# Sheet_2.net
KiCad netlist of a schematic drawn in Altium Designer
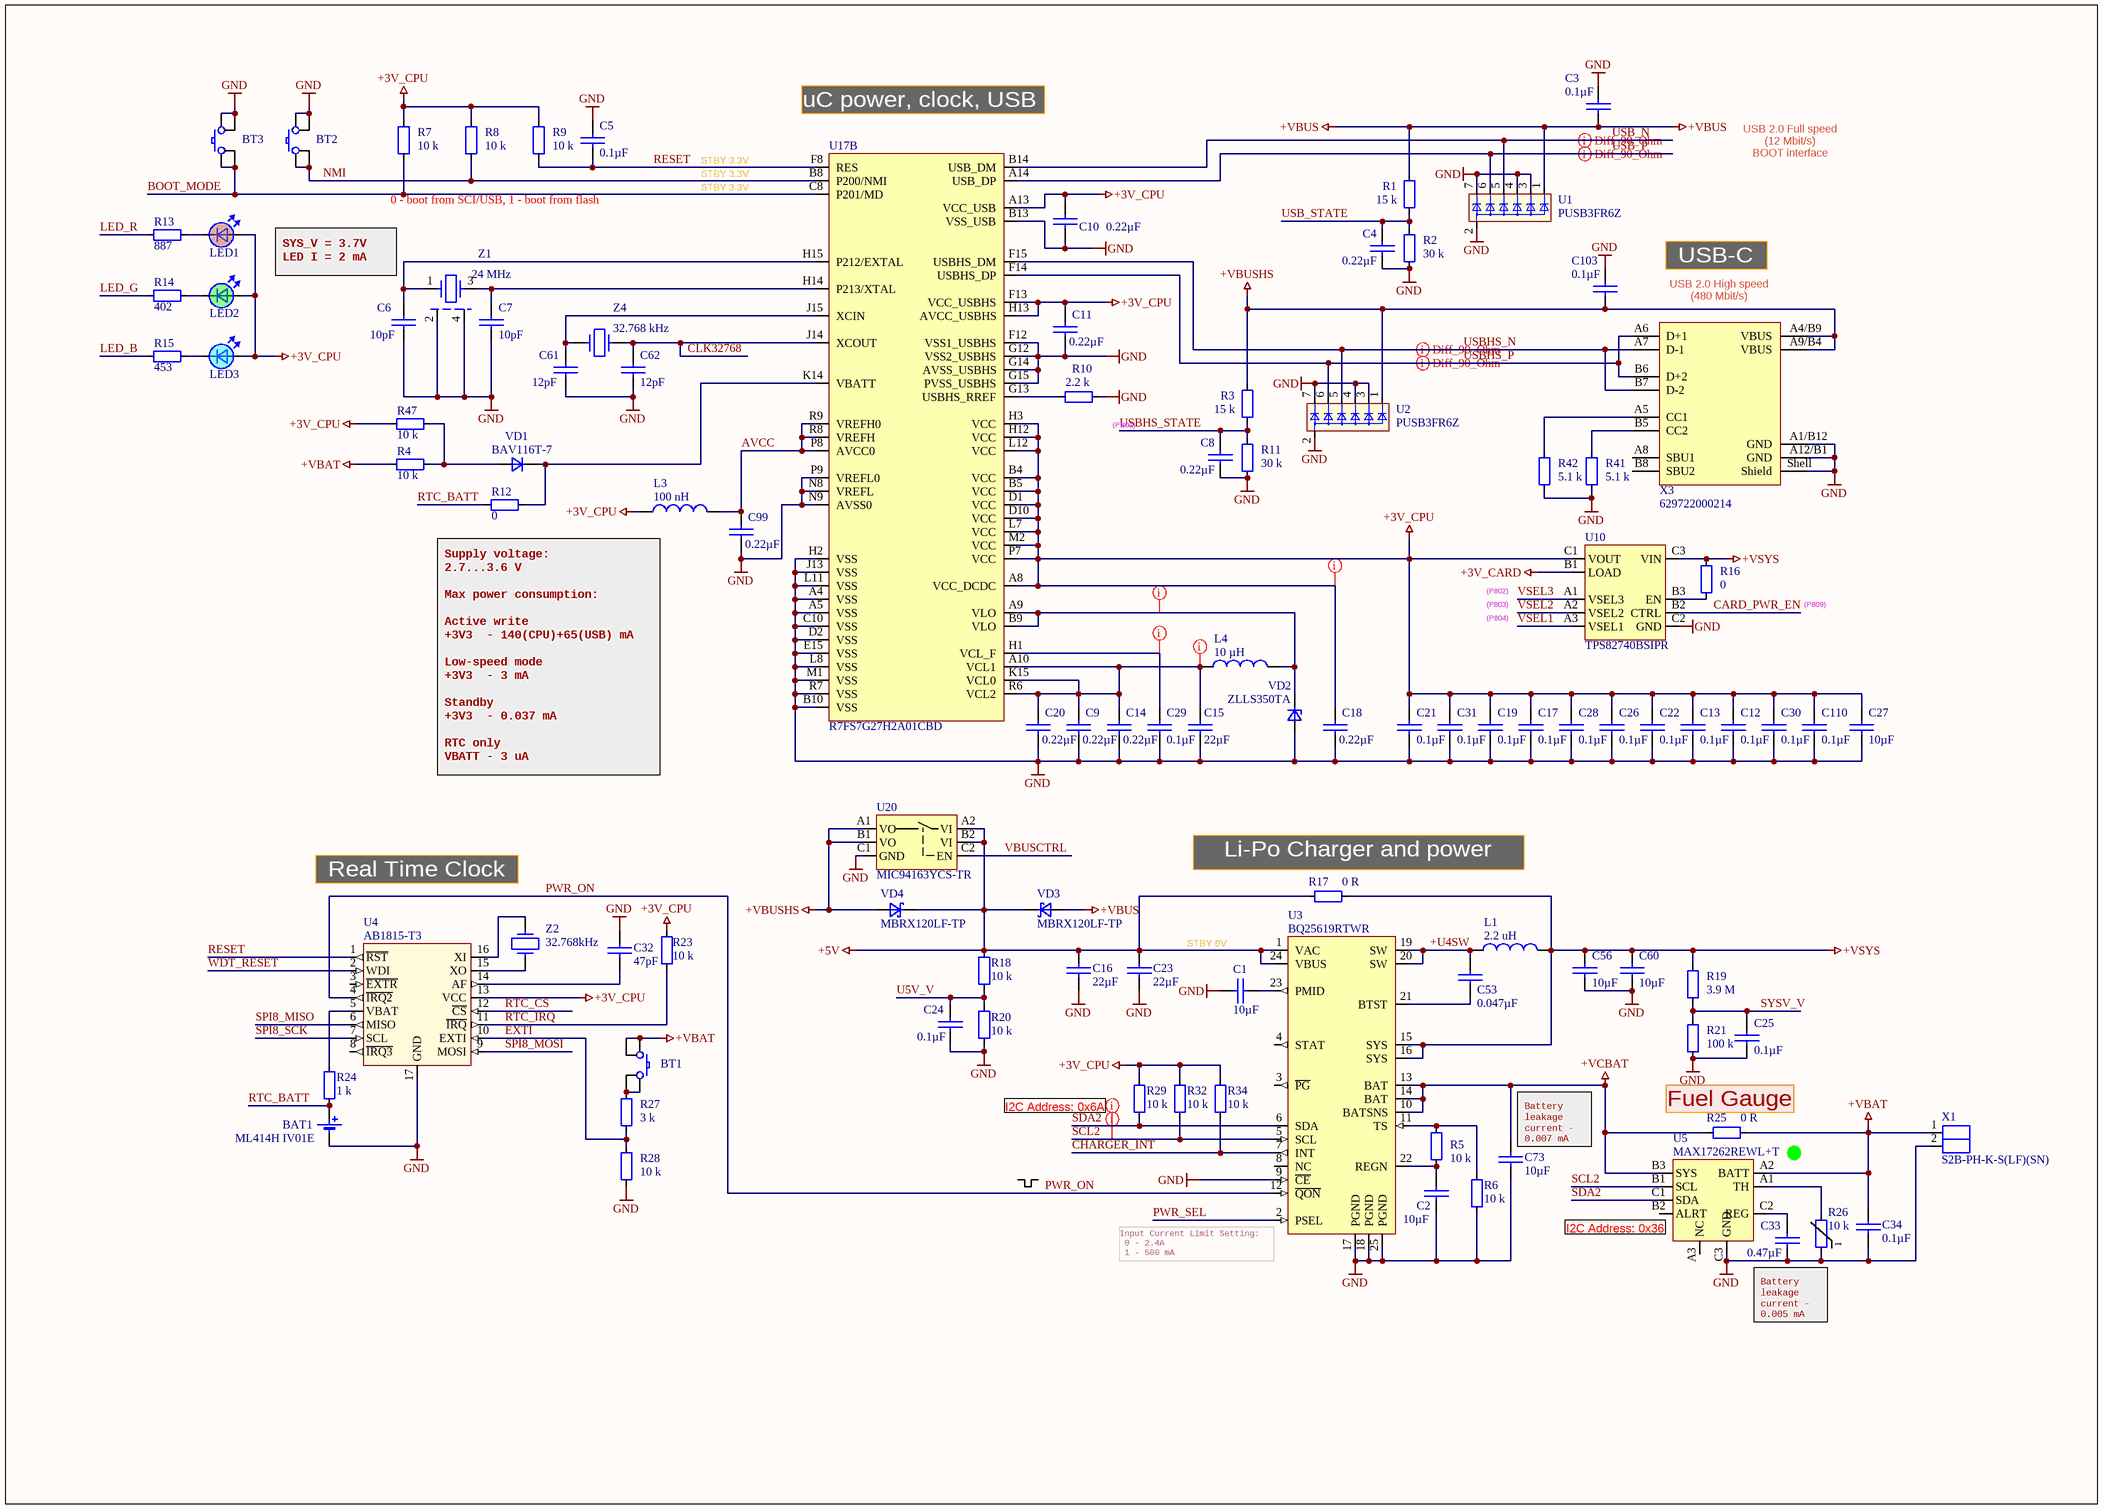
[diagram p0: Sheet_2.SchDoc]

(export (version "E")
  (design (tool "Eeschema 10.0.6"))
  (components
    (comp (ref "BAT1")
      (value "ML414H IV01E")
      (footprint "ML414H")
      (description "Coin, 4.8mm 3V Lithium Battery Rechargeable (Secondary) 1mAh")
      (fields (field (name "PARTNUM") "728-1052-1-ND") (field (name "MANUFACTURER") "Seiko Instruments"))
      (libsource (lib "ea_PowerSources") (part "ML414H IV01E"))
    )
    (comp (ref "BT1")
      (value "EVP-AVAA1A")
      (footprint "EVPAV")
      (description "Tactile Switch SPST-NO Side Actuated Edge Mount, Right Angle")
      (fields
        (field (name "MANUFACTURER") "Panasonic Electronic Components")
        (field (name "PARTNUM") "P16849CT-ND")
      )
      (libsource (lib "ea_Buttons") (part "EVP-AVAA1A"))
    )
    (comp (ref "BT2")
      (value "EVP-AVAA1A")
      (footprint "EVPAV")
      (description "Tactile Switch SPST-NO Side Actuated Edge Mount, Right Angle")
      (fields
        (field (name "MANUFACTURER") "Panasonic Electronic Components")
        (field (name "PARTNUM") "P16849CT-ND")
      )
      (libsource (lib "ea_Buttons") (part "EVP-AVAA1A"))
    )
    (comp (ref "BT3")
      (value "EVP-AVAA1A")
      (footprint "EVPAV")
      (description "Tactile Switch SPST-NO Side Actuated Edge Mount, Right Angle")
      (fields
        (field (name "MANUFACTURER") "Panasonic Electronic Components")
        (field (name "PARTNUM") "P16849CT-ND")
      )
      (libsource (lib "ea_Buttons") (part "EVP-AVAA1A"))
    )
    (comp (ref "C1")
      (value "10µF")
      (footprint "0603 CAP")
      (description "10µF, ±10%, 16V, X5R, 0603 (1608 Metric), -55°C ~ 85°C, -, Automotive")
      (fields
        (field (name "PART NUMBER") "GRT188R61C106KE13D")
        (field (name "MANUFACTURER") "Murata Electronics North America")
      )
      (libsource (lib "ea_PassivComps") (part "Capacitor"))
    )
    (comp (ref "C2")
      (value "10µF")
      (footprint "0603 CAP")
      (description "10µF, ±10%, 16V, X5R, 0603 (1608 Metric), -55°C ~ 85°C, -, Automotive")
      (fields
        (field (name "PART NUMBER") "GRT188R61C106KE13D")
        (field (name "MANUFACTURER") "Murata Electronics North America")
      )
      (libsource (lib "ea_PassivComps") (part "Capacitor"))
    )
    (comp (ref "C3")
      (value "0.1µF")
      (footprint "0402 CAP")
      (description "0.1µF, ±10%, 50V, X7R, 0402 (1005 Metric), -55°C ~ 125°C, -, General Purpose")
      (fields
        (field (name "PART NUMBER") "0402B104K500CT")
        (field (name "MANUFACTURER") "Walsin Technology Corporation")
      )
      (libsource (lib "ea_PassivComps") (part "Capacitor"))
    )
    (comp (ref "C4")
      (value "0.22µF")
      (footprint "0402 CAP")
      (description "0.22µF, ±10%, 25V, X5R, 0402 (1005 Metric), -55°C ~ 85°C, -, Automotive")
      (fields
        (field (name "PART NUMBER") "GRT155R61E224KE01D")
        (field (name "MANUFACTURER") "Murata Electronics North America")
      )
      (libsource (lib "ea_PassivComps") (part "Capacitor"))
    )
    (comp (ref "C5")
      (value "0.1µF")
      (footprint "0402 CAP")
      (description "0.1µF, ±10%, 50V, X7R, 0402 (1005 Metric), -55°C ~ 125°C, -, General Purpose")
      (fields
        (field (name "PART NUMBER") "0402B104K500CT")
        (field (name "MANUFACTURER") "Walsin Technology Corporation")
      )
      (libsource (lib "ea_PassivComps") (part "Capacitor"))
    )
    (comp (ref "C6")
      (value "10pF")
      (footprint "0402 CAP")
      (description "10pF, ±1%, 50V, C0G, NP0, 0402 (1005 Metric), -55°C ~ 125°C, -, Automotive")
      (fields
        (field (name "PART NUMBER") "GCM1555C1H100FA16D")
        (field (name "MANUFACTURER") "Murata Electronics North America")
      )
      (libsource (lib "ea_PassivComps") (part "Capacitor"))
    )
    (comp (ref "C7")
      (value "10pF")
      (footprint "0402 CAP")
      (description "10pF, ±1%, 50V, C0G, NP0, 0402 (1005 Metric), -55°C ~ 125°C, -, Automotive")
      (fields
        (field (name "PART NUMBER") "GCM1555C1H100FA16D")
        (field (name "MANUFACTURER") "Murata Electronics North America")
      )
      (libsource (lib "ea_PassivComps") (part "Capacitor"))
    )
    (comp (ref "C8")
      (value "0.22µF")
      (footprint "0402 CAP")
      (description "0.22µF, ±10%, 25V, X5R, 0402 (1005 Metric), -55°C ~ 85°C, -, Automotive")
      (fields
        (field (name "PART NUMBER") "GRT155R61E224KE01D")
        (field (name "MANUFACTURER") "Murata Electronics North America")
      )
      (libsource (lib "ea_PassivComps") (part "Capacitor"))
    )
    (comp (ref "C9")
      (value "0.22µF")
      (footprint "0402 CAP")
      (description "0.22µF, ±10%, 25V, X5R, 0402 (1005 Metric), -55°C ~ 85°C, -, Automotive")
      (fields
        (field (name "PART NUMBER") "GRT155R61E224KE01D")
        (field (name "MANUFACTURER") "Murata Electronics North America")
      )
      (libsource (lib "ea_PassivComps") (part "Capacitor"))
    )
    (comp (ref "C10")
      (value "0.22µF")
      (footprint "0402 CAP")
      (description "0.22µF, ±10%, 25V, X5R, 0402 (1005 Metric), -55°C ~ 85°C, -, Automotive")
      (fields
        (field (name "PART NUMBER") "GRT155R61E224KE01D")
        (field (name "MANUFACTURER") "Murata Electronics North America")
      )
      (libsource (lib "ea_PassivComps") (part "Capacitor"))
    )
    (comp (ref "C11")
      (value "0.22µF")
      (footprint "0402 CAP")
      (description "0.22µF, ±10%, 25V, X5R, 0402 (1005 Metric), -55°C ~ 85°C, -, Automotive")
      (fields
        (field (name "PART NUMBER") "GRT155R61E224KE01D")
        (field (name "MANUFACTURER") "Murata Electronics North America")
      )
      (libsource (lib "ea_PassivComps") (part "Capacitor"))
    )
    (comp (ref "C12")
      (value "0.1µF")
      (footprint "0402 CAP")
      (description "0.1µF, ±10%, 50V, X7R, 0402 (1005 Metric), -55°C ~ 125°C, -, General Purpose")
      (fields
        (field (name "PART NUMBER") "0402B104K500CT")
        (field (name "MANUFACTURER") "Walsin Technology Corporation")
      )
      (libsource (lib "ea_PassivComps") (part "Capacitor"))
    )
    (comp (ref "C13")
      (value "0.1µF")
      (footprint "0402 CAP")
      (description "0.1µF, ±10%, 50V, X7R, 0402 (1005 Metric), -55°C ~ 125°C, -, General Purpose")
      (fields
        (field (name "PART NUMBER") "0402B104K500CT")
        (field (name "MANUFACTURER") "Walsin Technology Corporation")
      )
      (libsource (lib "ea_PassivComps") (part "Capacitor"))
    )
    (comp (ref "C14")
      (value "0.22µF")
      (footprint "0402 CAP")
      (description "0.22µF, ±10%, 25V, X5R, 0402 (1005 Metric), -55°C ~ 85°C, -, Automotive")
      (fields
        (field (name "PART NUMBER") "GRT155R61E224KE01D")
        (field (name "MANUFACTURER") "Murata Electronics North America")
      )
      (libsource (lib "ea_PassivComps") (part "Capacitor"))
    )
    (comp (ref "C15")
      (value "22µF")
      (footprint "0402 CAP")
      (description "22µF, ±20%, 6.3V, X5R, 0402 (1005 Metric), -55°C ~ 85°C, -, General Purpose")
      (fields
        (field (name "PART NUMBER") "CL05A226MQ5N6J8")
        (field (name "MANUFACTURER") "Samsung Electro-Mechanics")
      )
      (libsource (lib "ea_PassivComps") (part "Capacitor"))
    )
    (comp (ref "C16")
      (value "22µF")
      (footprint "0603 CAP")
      (description "22µF, ±20%, 10V, X5R, 0603 (1608 Metric), -55°C ~ 85°C, -, SMPS Filtering")
      (fields (field (name "PART NUMBER") "LMK107BBJ226MA-T") (field (name "MANUFACTURER") "Taiyo Yuden"))
      (libsource (lib "ea_PassivComps") (part "Capacitor"))
    )
    (comp (ref "C17")
      (value "0.1µF")
      (footprint "0402 CAP")
      (description "0.1µF, ±10%, 50V, X7R, 0402 (1005 Metric), -55°C ~ 125°C, -, General Purpose")
      (fields
        (field (name "PART NUMBER") "0402B104K500CT")
        (field (name "MANUFACTURER") "Walsin Technology Corporation")
      )
      (libsource (lib "ea_PassivComps") (part "Capacitor"))
    )
    (comp (ref "C18")
      (value "0.22µF")
      (footprint "0402 CAP")
      (description "0.22µF, ±10%, 25V, X5R, 0402 (1005 Metric), -55°C ~ 85°C, -, Automotive")
      (fields
        (field (name "PART NUMBER") "GRT155R61E224KE01D")
        (field (name "MANUFACTURER") "Murata Electronics North America")
      )
      (libsource (lib "ea_PassivComps") (part "Capacitor"))
    )
    (comp (ref "C19")
      (value "0.1µF")
      (footprint "0402 CAP")
      (description "0.1µF, ±10%, 50V, X7R, 0402 (1005 Metric), -55°C ~ 125°C, -, General Purpose")
      (fields
        (field (name "PART NUMBER") "0402B104K500CT")
        (field (name "MANUFACTURER") "Walsin Technology Corporation")
      )
      (libsource (lib "ea_PassivComps") (part "Capacitor"))
    )
    (comp (ref "C20")
      (value "0.22µF")
      (footprint "0402 CAP")
      (description "0.22µF, ±10%, 25V, X5R, 0402 (1005 Metric), -55°C ~ 85°C, -, Automotive")
      (fields
        (field (name "PART NUMBER") "GRT155R61E224KE01D")
        (field (name "MANUFACTURER") "Murata Electronics North America")
      )
      (libsource (lib "ea_PassivComps") (part "Capacitor"))
    )
    (comp (ref "C21")
      (value "0.1µF")
      (footprint "0402 CAP")
      (description "0.1µF, ±10%, 50V, X7R, 0402 (1005 Metric), -55°C ~ 125°C, -, General Purpose")
      (fields
        (field (name "PART NUMBER") "0402B104K500CT")
        (field (name "MANUFACTURER") "Walsin Technology Corporation")
      )
      (libsource (lib "ea_PassivComps") (part "Capacitor"))
    )
    (comp (ref "C22")
      (value "0.1µF")
      (footprint "0402 CAP")
      (description "0.1µF, ±10%, 50V, X7R, 0402 (1005 Metric), -55°C ~ 125°C, -, General Purpose")
      (fields
        (field (name "PART NUMBER") "0402B104K500CT")
        (field (name "MANUFACTURER") "Walsin Technology Corporation")
      )
      (libsource (lib "ea_PassivComps") (part "Capacitor"))
    )
    (comp (ref "C23")
      (value "22µF")
      (footprint "0603 CAP")
      (description "22µF, ±20%, 10V, X5R, 0603 (1608 Metric), -55°C ~ 85°C, -, SMPS Filtering")
      (fields (field (name "PART NUMBER") "LMK107BBJ226MA-T") (field (name "MANUFACTURER") "Taiyo Yuden"))
      (libsource (lib "ea_PassivComps") (part "Capacitor"))
    )
    (comp (ref "C24")
      (value "0.1µF")
      (footprint "0402 CAP")
      (description "0.1µF, ±10%, 50V, X7R, 0402 (1005 Metric), -55°C ~ 125°C, -, General Purpose")
      (fields
        (field (name "PART NUMBER") "0402B104K500CT")
        (field (name "MANUFACTURER") "Walsin Technology Corporation")
      )
      (libsource (lib "ea_PassivComps") (part "Capacitor"))
    )
    (comp (ref "C25")
      (value "0.1µF")
      (footprint "0402 CAP")
      (description "0.1µF, ±10%, 50V, X7R, 0402 (1005 Metric), -55°C ~ 125°C, -, General Purpose")
      (fields
        (field (name "PART NUMBER") "0402B104K500CT")
        (field (name "MANUFACTURER") "Walsin Technology Corporation")
      )
      (libsource (lib "ea_PassivComps") (part "Capacitor"))
    )
    (comp (ref "C26")
      (value "0.1µF")
      (footprint "0402 CAP")
      (description "0.1µF, ±10%, 50V, X7R, 0402 (1005 Metric), -55°C ~ 125°C, -, General Purpose")
      (fields
        (field (name "PART NUMBER") "0402B104K500CT")
        (field (name "MANUFACTURER") "Walsin Technology Corporation")
      )
      (libsource (lib "ea_PassivComps") (part "Capacitor"))
    )
    (comp (ref "C27")
      (value "10µF")
      (footprint "0603 CAP")
      (description "10µF, ±10%, 16V, X5R, 0603 (1608 Metric), -55°C ~ 85°C, -, Automotive")
      (fields
        (field (name "PART NUMBER") "GRT188R61C106KE13D")
        (field (name "MANUFACTURER") "Murata Electronics North America")
      )
      (libsource (lib "ea_PassivComps") (part "Capacitor"))
    )
    (comp (ref "C28")
      (value "0.1µF")
      (footprint "0402 CAP")
      (description "0.1µF, ±10%, 50V, X7R, 0402 (1005 Metric), -55°C ~ 125°C, -, General Purpose")
      (fields
        (field (name "PART NUMBER") "0402B104K500CT")
        (field (name "MANUFACTURER") "Walsin Technology Corporation")
      )
      (libsource (lib "ea_PassivComps") (part "Capacitor"))
    )
    (comp (ref "C29")
      (value "0.1µF")
      (footprint "0402 CAP")
      (description "0.1µF, ±10%, 50V, X7R, 0402 (1005 Metric), -55°C ~ 125°C, -, General Purpose")
      (fields
        (field (name "PART NUMBER") "0402B104K500CT")
        (field (name "MANUFACTURER") "Walsin Technology Corporation")
      )
      (libsource (lib "ea_PassivComps") (part "Capacitor"))
    )
    (comp (ref "C30")
      (value "0.1µF")
      (footprint "0402 CAP")
      (description "0.1µF, ±10%, 50V, X7R, 0402 (1005 Metric), -55°C ~ 125°C, -, General Purpose")
      (fields
        (field (name "PART NUMBER") "0402B104K500CT")
        (field (name "MANUFACTURER") "Walsin Technology Corporation")
      )
      (libsource (lib "ea_PassivComps") (part "Capacitor"))
    )
    (comp (ref "C31")
      (value "0.1µF")
      (footprint "0402 CAP")
      (description "0.1µF, ±10%, 50V, X7R, 0402 (1005 Metric), -55°C ~ 125°C, -, General Purpose")
      (fields
        (field (name "PART NUMBER") "0402B104K500CT")
        (field (name "MANUFACTURER") "Walsin Technology Corporation")
      )
      (libsource (lib "ea_PassivComps") (part "Capacitor"))
    )
    (comp (ref "C32")
      (value "47pF")
      (footprint "0402 CAP")
      (fields
        (field (name "PART NUMBER") "GJM1555C1H470FB01D")
        (field (name "MANUFACTURER") "Murata Electronics North America")
        (field (name "PARTNUM") "490-16376-1-ND")
      )
      (libsource (lib "ea_PassivComps") (part "Capacitor"))
    )
    (comp (ref "C33")
      (value "0.47µF")
      (footprint "0402 CAP")
      (description "0.47µF, ±20%, 25V, X5R, 0402 (1005 Metric), -55°C ~ 85°C, -, Automotive")
      (fields
        (field (name "PART NUMBER") "GRT155R61E474ME01D")
        (field (name "MANUFACTURER") "Murata Electronics North America")
      )
      (libsource (lib "ea_PassivComps") (part "Capacitor"))
    )
    (comp (ref "C34")
      (value "0.1µF")
      (footprint "0402 CAP")
      (description "0.1µF, ±10%, 50V, X7R, 0402 (1005 Metric), -55°C ~ 125°C, -, General Purpose")
      (fields
        (field (name "PART NUMBER") "0402B104K500CT")
        (field (name "MANUFACTURER") "Walsin Technology Corporation")
      )
      (libsource (lib "ea_PassivComps") (part "Capacitor"))
    )
    (comp (ref "C53")
      (value "0.047µF")
      (footprint "0402 CAP")
      (description "0.047µF, ±10%, 25V, X7R, 0402 (1005 Metric), -55°C ~ 125°C, -, General Purpose")
      (fields (field (name "PART NUMBER") "CC0402KRX7R8BB473") (field (name "MANUFACTURER") "Yageo"))
      (libsource (lib "ea_PassivComps") (part "Capacitor"))
    )
    (comp (ref "C56")
      (value "10µF")
      (footprint "0603 CAP")
      (description "10µF, ±10%, 16V, X5R, 0603 (1608 Metric), -55°C ~ 85°C, -, Automotive")
      (fields
        (field (name "PART NUMBER") "GRT188R61C106KE13D")
        (field (name "MANUFACTURER") "Murata Electronics North America")
      )
      (libsource (lib "ea_PassivComps") (part "Capacitor"))
    )
    (comp (ref "C60")
      (value "10µF")
      (footprint "0603 CAP")
      (description "10µF, ±10%, 16V, X5R, 0603 (1608 Metric), -55°C ~ 85°C, -, Automotive")
      (fields
        (field (name "PART NUMBER") "GRT188R61C106KE13D")
        (field (name "MANUFACTURER") "Murata Electronics North America")
      )
      (libsource (lib "ea_PassivComps") (part "Capacitor"))
    )
    (comp (ref "C61")
      (value "12pF")
      (footprint "0402 CAP")
      (description "12pF, ±2%, 50V, C0G, NP0, 0402 (1005 Metric), -55°C ~ 125°C, -, General Purpose")
      (fields
        (field (name "PART NUMBER") "0402N120G500CT")
        (field (name "MANUFACTURER") "Walsin Technology Corporation")
      )
      (libsource (lib "ea_PassivComps") (part "Capacitor"))
    )
    (comp (ref "C62")
      (value "12pF")
      (footprint "0402 CAP")
      (description "12pF, ±2%, 50V, C0G, NP0, 0402 (1005 Metric), -55°C ~ 125°C, -, General Purpose")
      (fields
        (field (name "PART NUMBER") "0402N120G500CT")
        (field (name "MANUFACTURER") "Walsin Technology Corporation")
      )
      (libsource (lib "ea_PassivComps") (part "Capacitor"))
    )
    (comp (ref "C73")
      (value "10µF")
      (footprint "0603 CAP")
      (description "10µF, ±10%, 16V, X5R, 0603 (1608 Metric), -55°C ~ 85°C, -, Automotive")
      (fields
        (field (name "PART NUMBER") "GRT188R61C106KE13D")
        (field (name "MANUFACTURER") "Murata Electronics North America")
      )
      (libsource (lib "ea_PassivComps") (part "Capacitor"))
    )
    (comp (ref "C99")
      (value "0.22µF")
      (footprint "0402 CAP")
      (description "0.22µF, ±10%, 25V, X5R, 0402 (1005 Metric), -55°C ~ 85°C, -, Automotive")
      (fields
        (field (name "PART NUMBER") "GRT155R61E224KE01D")
        (field (name "MANUFACTURER") "Murata Electronics North America")
      )
      (libsource (lib "ea_PassivComps") (part "Capacitor"))
    )
    (comp (ref "C103")
      (value "0.1µF")
      (footprint "0402 CAP")
      (description "0.1µF, ±10%, 50V, X7R, 0402 (1005 Metric), -55°C ~ 125°C, -, General Purpose")
      (fields
        (field (name "PART NUMBER") "0402B104K500CT")
        (field (name "MANUFACTURER") "Walsin Technology Corporation")
      )
      (libsource (lib "ea_PassivComps") (part "Capacitor"))
    )
    (comp (ref "C110")
      (value "0.1µF")
      (footprint "0402 CAP")
      (description "0.1µF, ±10%, 50V, X7R, 0402 (1005 Metric), -55°C ~ 125°C, -, General Purpose")
      (fields
        (field (name "PART NUMBER") "0402B104K500CT")
        (field (name "MANUFACTURER") "Walsin Technology Corporation")
      )
      (libsource (lib "ea_PassivComps") (part "Capacitor"))
    )
    (comp (ref "L1")
      (value "2.2 uH")
      (footprint "IHLP-2020BZ-11")
      (description "2.2 uH, 4.2 A, 50 mOhms, +-20%,-55.. +125 C")
      (fields (field (name "MANUFACTURER") "Vishay Dale") (field (name "PARTNUM") "541-1088-1-ND"))
      (libsource (lib "ea_Inductors") (part "IHLP2020BZER2R2M01"))
    )
    (comp (ref "L3")
      (value "100 nH")
      (footprint "INDC1005-0402")
      (description "100nH, ±5%, 200 мА, 2 Ohm, 0402, -55..+125 C")
      (fields (field (name "MANUFACTURER") "TDK Corporation") (field (name "TOLERANCE") "±5%"))
      (libsource (lib "ea_Inductors") (part "MLG1005SR10JT000"))
    )
    (comp (ref "L4")
      (value "10 µH")
      (footprint "SRU3017")
      (description "10µH Shielded Wirewound Inductor 850mA 120mOhm Nonstandard, -40...+125 C")
      (fields (field (name "MANUFACTURER") "Bourns Inc.") (field (name "PARTNUM") "SRU3017-100YCT-ND"))
      (libsource (lib "ea_Inductors") (part "SRU3017-100Y"))
    )
    (comp (ref "LED1")
      (value "APHHS1005LSECK/J3-PF")
      (footprint "2-SMD RED")
      (description "Red 625nm LED Indication - Discrete 1.8V, 2 mA,  0402 (1005 Metric)")
      (fields (field (name "MANUFACTURER") "Kingbright") (field (name "PARTNUM") "754-2123-1-ND"))
      (libsource (lib "ea_Indicators") (part "APHHS1005LSECK/J3-PF"))
    )
    (comp (ref "LED2")
      (value "APHHS1005LZGCK-V")
      (footprint "2-SMD GREEN")
      (description "Green 525nm LED Indication - Discrete 2.65V, 2mA, 0402 (1005 Metric)")
      (fields (field (name "MANUFACTURER") "Kingbright") (field (name "PARTNUM") "754-2126-1-ND"))
      (libsource (lib "ea_Indicators") (part "APHHS1005LZGCK-V"))
    )
    (comp (ref "LED3")
      (value "APHHS1005LQBC/D-V")
      (footprint "2-SMD BLUE")
      (description "Blue 465nm LED Indication - Discrete 2.2V, 2mA, 0402 (1005 Metric)")
      (fields (field (name "MANUFACTURER") "Kingbright") (field (name "PARTNUM") "754-2122-1-ND"))
      (libsource (lib "ea_Indicators") (part "APHHS1005LQBC/D-V"))
    )
    (comp (ref "R1")
      (value "15 k")
      (footprint "0402")
      (fields
        (field (name "MANUFACTURER") "Stackpole Electronics Inc")
        (field (name "TOLERANCE") "±1%")
        (field (name "VOLTAGE") "75V")
      )
      (libsource (lib "") (part "Resistor_2"))
    )
    (comp (ref "R2")
      (value "30 k")
      (footprint "0402")
      (fields
        (field (name "MANUFACTURER") "Stackpole Electronics Inc")
        (field (name "TOLERANCE") "±1%")
        (field (name "VOLTAGE") "75V")
      )
      (libsource (lib "") (part "Resistor_2"))
    )
    (comp (ref "R3")
      (value "15 k")
      (footprint "0402")
      (fields
        (field (name "MANUFACTURER") "Stackpole Electronics Inc")
        (field (name "TOLERANCE") "±1%")
        (field (name "VOLTAGE") "75V")
      )
      (libsource (lib "") (part "Resistor_2"))
    )
    (comp (ref "R4")
      (value "10 k")
      (footprint "0402")
      (fields
        (field (name "MANUFACTURER") "Stackpole Electronics Inc")
        (field (name "TOLERANCE") "±1%")
        (field (name "VOLTAGE") "75V")
      )
      (libsource (lib "") (part "Resistor_2"))
    )
    (comp (ref "R5")
      (value "10 k")
      (footprint "0402")
      (fields
        (field (name "MANUFACTURER") "Stackpole Electronics Inc")
        (field (name "TOLERANCE") "±1%")
        (field (name "VOLTAGE") "75V")
      )
      (libsource (lib "") (part "Resistor_3"))
    )
    (comp (ref "R6")
      (value "10 k")
      (footprint "0402")
      (fields
        (field (name "MANUFACTURER") "Stackpole Electronics Inc")
        (field (name "TOLERANCE") "±1%")
        (field (name "VOLTAGE") "75V")
      )
      (libsource (lib "ea_PassivComps") (part "Resistor"))
    )
    (comp (ref "R7")
      (value "10 k")
      (footprint "0402")
      (fields
        (field (name "MANUFACTURER") "Stackpole Electronics Inc")
        (field (name "TOLERANCE") "±1%")
        (field (name "VOLTAGE") "75V")
      )
      (libsource (lib "ea_PassivComps") (part "Resistor"))
    )
    (comp (ref "R8")
      (value "10 k")
      (footprint "0402")
      (fields
        (field (name "MANUFACTURER") "Stackpole Electronics Inc")
        (field (name "TOLERANCE") "±1%")
        (field (name "VOLTAGE") "75V")
      )
      (libsource (lib "ea_PassivComps") (part "Resistor"))
    )
    (comp (ref "R9")
      (value "10 k")
      (footprint "0402")
      (fields
        (field (name "MANUFACTURER") "Stackpole Electronics Inc")
        (field (name "TOLERANCE") "±1%")
        (field (name "VOLTAGE") "75V")
      )
      (libsource (lib "ea_PassivComps") (part "Resistor"))
    )
    (comp (ref "R10")
      (value "2.2 k")
      (footprint "0402")
      (fields
        (field (name "MANUFACTURER") "Stackpole Electronics Inc")
        (field (name "TOLERANCE") "±1%")
        (field (name "VOLTAGE") "75V")
      )
      (libsource (lib "") (part "Resistor_1"))
    )
    (comp (ref "R11")
      (value "30 k")
      (footprint "0402")
      (fields
        (field (name "MANUFACTURER") "Stackpole Electronics Inc")
        (field (name "TOLERANCE") "±1%")
        (field (name "VOLTAGE") "75V")
      )
      (libsource (lib "") (part "Resistor_2"))
    )
    (comp (ref "R12")
      (value "0")
      (footprint "0402")
      (description "0 Ohms Jumper 0.063W, 1/16W Chip Resistor 0402 (1005 Metric) Thick Film")
      (fields (field (name "MANUFACTURER") "Walsin Technology Corporation") (field (name "VOLTAGE") "50 V"))
      (libsource (lib "") (part "WR04X000 PTL_1"))
    )
    (comp (ref "R13")
      (value "887")
      (footprint "0402")
      (fields
        (field (name "MANUFACTURER") "Stackpole Electronics Inc")
        (field (name "TOLERANCE") "±1%")
        (field (name "VOLTAGE") "75V")
      )
      (libsource (lib "") (part "Resistor_1"))
    )
    (comp (ref "R14")
      (value "402")
      (footprint "0402")
      (fields
        (field (name "MANUFACTURER") "Stackpole Electronics Inc")
        (field (name "TOLERANCE") "±1%")
        (field (name "VOLTAGE") "75V")
      )
      (libsource (lib "") (part "Resistor_1"))
    )
    (comp (ref "R15")
      (value "453")
      (footprint "0402")
      (fields
        (field (name "MANUFACTURER") "Stackpole Electronics Inc")
        (field (name "TOLERANCE") "±1%")
        (field (name "VOLTAGE") "75V")
      )
      (libsource (lib "") (part "Resistor_1"))
    )
    (comp (ref "R16")
      (value "0")
      (footprint "0402")
      (description "0 Ohms Jumper 0.063W, 1/16W Chip Resistor 0402 (1005 Metric) Thick Film")
      (fields (field (name "MANUFACTURER") "Walsin Technology Corporation") (field (name "VOLTAGE") "50 V"))
      (libsource (lib "ea_Resistors_0402") (part "WR04X000 PTL"))
    )
    (comp (ref "R17")
      (value "0 R")
      (footprint "0603")
      (fields
        (field (name "MANUFACTURER") "KOA Speer Electronics, Inc.")
        (field (name "PARTNUM") "2019-RK73Z1JTTDCT-ND")
        (field (name "Comment") "RK73Z1JTTD")
      )
      (libsource (lib "ea_Resistors_0603") (part "RK73Z1JTTD"))
    )
    (comp (ref "R18")
      (value "10 k")
      (footprint "0402")
      (fields
        (field (name "MANUFACTURER") "Stackpole Electronics Inc")
        (field (name "TOLERANCE") "±1%")
        (field (name "VOLTAGE") "75V")
      )
      (libsource (lib "") (part "Resistor_2"))
    )
    (comp (ref "R19")
      (value "3.9 M")
      (footprint "0402")
      (fields
        (field (name "MANUFACTURER") "Vishay Dale")
        (field (name "TOLERANCE") "±1%")
        (field (name "VOLTAGE") "75V")
      )
      (libsource (lib "") (part "Resistor_3"))
    )
    (comp (ref "R20")
      (value "10 k")
      (footprint "0402")
      (fields
        (field (name "MANUFACTURER") "Stackpole Electronics Inc")
        (field (name "TOLERANCE") "±1%")
        (field (name "VOLTAGE") "75V")
      )
      (libsource (lib "") (part "Resistor_2"))
    )
    (comp (ref "R21")
      (value "100 k")
      (footprint "0402")
      (fields
        (field (name "MANUFACTURER") "Yageo")
        (field (name "TOLERANCE") "±1%")
        (field (name "VOLTAGE") "75V")
      )
      (libsource (lib "") (part "Resistor_3"))
    )
    (comp (ref "R23")
      (value "10 k")
      (footprint "0402")
      (fields
        (field (name "MANUFACTURER") "Stackpole Electronics Inc")
        (field (name "TOLERANCE") "±1%")
        (field (name "VOLTAGE") "75V")
      )
      (libsource (lib "") (part "Resistor_3"))
    )
    (comp (ref "R24")
      (value "1 k")
      (footprint "0402")
      (fields
        (field (name "MANUFACTURER") "Yageo")
        (field (name "TOLERANCE") "±1%")
        (field (name "VOLTAGE") "75V")
      )
      (libsource (lib "ea_PassivComps") (part "Resistor"))
    )
    (comp (ref "R25")
      (value "0 R")
      (footprint "0603")
      (description "0 Ohms Jumper 0.1W, 1/10W Chip Resistor 0603 (1608 Metric) - Thick Film")
      (fields (field (name "MANUFACTURER") "Venkel") (field (name "VOLTAGE") "75 V"))
      (libsource (lib "ea_Resistors_0603") (part "CR0603-10W-000T"))
    )
    (comp (ref "R26")
      (value "10 k")
      (footprint "0402")
      (description "NTC Thermistor 10k , B25/85=3435K,  -40°C ~ 125°C")
      (fields (field (name "MANUFACTURER") "TDK Corporation") (field (name "TOLERANCE") "±0.5%"))
      (libsource (lib "ea_Resistors_0402") (part "NTCG103JX103DTDS"))
    )
    (comp (ref "R27")
      (value "3 k")
      (footprint "0402")
      (fields
        (field (name "MANUFACTURER") "Yageo")
        (field (name "TOLERANCE") "±1%")
        (field (name "VOLTAGE") "75V")
      )
      (libsource (lib "ea_PassivComps") (part "Resistor"))
    )
    (comp (ref "R28")
      (value "10 k")
      (footprint "0402")
      (fields
        (field (name "MANUFACTURER") "Stackpole Electronics Inc")
        (field (name "TOLERANCE") "±1%")
        (field (name "VOLTAGE") "75V")
      )
      (libsource (lib "ea_PassivComps") (part "Resistor"))
    )
    (comp (ref "R29")
      (value "10 k")
      (footprint "0402")
      (fields
        (field (name "MANUFACTURER") "Stackpole Electronics Inc")
        (field (name "TOLERANCE") "±1%")
        (field (name "VOLTAGE") "75V")
      )
      (libsource (lib "ea_PassivComps") (part "Resistor"))
    )
    (comp (ref "R32")
      (value "10 k")
      (footprint "0402")
      (fields
        (field (name "MANUFACTURER") "Stackpole Electronics Inc")
        (field (name "TOLERANCE") "±1%")
        (field (name "VOLTAGE") "75V")
      )
      (libsource (lib "ea_PassivComps") (part "Resistor"))
    )
    (comp (ref "R34")
      (value "10 k")
      (footprint "0402")
      (fields
        (field (name "MANUFACTURER") "Stackpole Electronics Inc")
        (field (name "TOLERANCE") "±1%")
        (field (name "VOLTAGE") "75V")
      )
      (libsource (lib "ea_PassivComps") (part "Resistor"))
    )
    (comp (ref "R41")
      (value "5.1 k")
      (footprint "0402")
      (fields
        (field (name "MANUFACTURER") "Stackpole Electronics Inc")
        (field (name "TOLERANCE") "±1%")
        (field (name "VOLTAGE") "75V")
      )
      (libsource (lib "") (part "Resistor_1"))
    )
    (comp (ref "R42")
      (value "5.1 k")
      (footprint "0402")
      (fields
        (field (name "MANUFACTURER") "Stackpole Electronics Inc")
        (field (name "TOLERANCE") "±1%")
        (field (name "VOLTAGE") "75V")
      )
      (libsource (lib "") (part "Resistor_1"))
    )
    (comp (ref "R47")
      (value "10 k")
      (footprint "0402")
      (fields
        (field (name "MANUFACTURER") "Stackpole Electronics Inc")
        (field (name "TOLERANCE") "±1%")
        (field (name "VOLTAGE") "75V")
      )
      (libsource (lib "") (part "Resistor_2"))
    )
    (comp (ref "U1")
      (value "PUSB3FR6Z")
      (footprint "SOT1358-1")
      (description "TVS Diode, 3V (Typ) Clamp 5A (8/20µs) Ipp ,  7-XSON (1.1x2.1), -40°C ~ 85°C (TA)")
      (fields (field (name "MANUFACTURER") "Nexperia USA Inc.") (field (name "PARTNUM") "1727-2027-1-ND"))
      (libsource (lib "ea_TVS_protection") (part "PUSB3FR6Z"))
    )
    (comp (ref "U2")
      (value "PUSB3FR6Z")
      (footprint "SOT1358-1")
      (description "TVS Diode, 3V (Typ) Clamp 5A (8/20µs) Ipp ,  7-XSON (1.1x2.1), -40°C ~ 85°C (TA)")
      (fields (field (name "MANUFACTURER") "Nexperia USA Inc.") (field (name "PARTNUM") "1727-2027-1-ND"))
      (libsource (lib "ea_TVS_protection") (part "PUSB3FR6Z"))
    )
    (comp (ref "U3")
      (value "BQ25619RTWR")
      (footprint "TI S-PVQFN-N24")
      (description "Charger IC Lithium Ion/Polymer 24-WQFN (4x4), -40...+85 C")
      (fields
        (field (name "PARTNUM") "296-BQ25619RTWRCT-ND")
        (field (name "MANUFACTURER") "Texas Instruments")
      )
      (libsource (lib "BQ25619") (part "BQ25619RTWR"))
    )
    (comp (ref "U4")
      (value "AB1815-T3")
      (footprint "QFN-16 3x3mm AB18XX")
      (description "Real Time Clock (RTC) IC Clock/Calendar 256B SPI, 16-VFQFN Exposed Pad, -40...+85 C")
      (fields (field (name "MANUFACTURER") "Abracon LLC") (field (name "PARTNUM") "535-11936-1-ND"))
      (libsource (lib "ea_IC_RTC") (part "AB1815-T3"))
    )
    (comp (ref "U5")
      (value "MAX17262REWL+T")
      (footprint "9-WFBGA")
      (description "Battery Fuel Gauge IC LiFePO4/Li-ion 9-WLP, -40°C ~ 85°C (TA)")
      (fields
        (field (name "MANUFACTURER") "Analog Devices Inc./Maxim Integrated")
        (field (name "PARTNUM") "175-MAX17262REWL+TCT-ND")
      )
      (libsource (lib "ea_IC_Chargers_Fuel_Gauges") (part "MAX17262REWL+T"))
    )
    (comp (ref "U10")
      (value "TPS82740BSIPR")
      (footprint "MicroSiP")
      (fields (field (name "MANUFACTURER") "Texas Instruments") (field (name "PARTNUM") "296-46481-1-ND"))
      (libsource (lib "ea_IC_Power_Reg_Ref_Sw") (part "TPS82740BSIPR"))
    )
    (comp (ref "U17")
      (value "R7FS7G27H2A01CBD")
      (footprint "RENESAS_FBGA224")
      (fields (field (name "MANUFACTURER") "Renesas") (field (name "PARTNUM") "R7FS7G27H2A01CBD#AC0-ND"))
      (libsource (lib "ea_IC_CPU") (part "R7FS7G27H2A01CBD#AC0"))
    )
    (comp (ref "U20")
      (value "MIC94163YCS-TR")
      (footprint "6-BALL WLCSP 1.5x1.0")
      (description "Power Switch/Driver 1:1 P-Channel 3A, 14.5mOhm,  6-WLCSP (1x1.5), -40°C ~ 125°C (TJ)")
      (fields (field (name "MANUFACTURER") "Microchip Technology") (field (name "PARTNUM") "576-4454-1-ND"))
      (libsource (lib "ea_IC_load_switches") (part "MIC94161YCS-TR"))
    )
    (comp (ref "VD1")
      (value "BAV116T-7")
      (footprint "SOD523")
      (description "Diode Standard 85V 100mA, 5nA @ 75V, SOD-523, -65°C ~ 150°C")
      (fields (field (name "MANUFACTURER") "Diodes Incorporated") (field (name "PARTNUM") "BAV116T-7DICT-ND"))
      (libsource (lib "ea_Diodes") (part "BAV116T-7"))
    )
    (comp (ref "VD2")
      (value "ZLLS350TA")
      (footprint "SOD523")
      (description "Diode Schottky 40V 380mA (DC) , Fast Recovery, SOD-523")
      (fields (field (name "MANUFACTURER") "Diodes Incorporated") (field (name "PARTNUM") "ZLLS350TACT-ND"))
      (libsource (lib "ea_Diodes") (part "ZLLS350TA"))
    )
    (comp (ref "VD3")
      (value "MBRX120LF-TP")
      (footprint "SOD-123")
      (description "Diode Schottky 20 V 1A, 360 mV @ 1 A ,  Surface Mount SOD-123, -65°C ~ 125°C")
      (fields
        (field (name "MANUFACTURER") "Micro Commercial Co")
        (field (name "PARTNUM") "MBRX120LF-TPMSCT-ND")
      )
      (libsource (lib "ea_Diodes") (part "MBRX120LF-TP"))
    )
    (comp (ref "VD4")
      (value "MBRX120LF-TP")
      (footprint "SOD-123")
      (description "Diode Schottky 20 V 1A, 360 mV @ 1 A ,  Surface Mount SOD-123, -65°C ~ 125°C")
      (fields
        (field (name "MANUFACTURER") "Micro Commercial Co")
        (field (name "PARTNUM") "MBRX120LF-TPMSCT-ND")
      )
      (libsource (lib "ea_Diodes") (part "MBRX120LF-TP"))
    )
    (comp (ref "X1")
      (value "S2B-PH-K-S(LF)(SN)")
      (footprint "S2B-PH-K-S")
      (description "Connector Header Through Hole, Right Angle 2 position 0.079\" (2.00mm)")
      (fields (field (name "MANUFACTURER") "JST Sales America Inc.") (field (name "PARTNUM") "455-1719-ND"))
      (libsource (lib "ea_Connectors_2.0_mm_pitch") (part "S2B-PH-K-S(LF)(SN)"))
    )
    (comp (ref "X3")
      (value "629722000214")
      (footprint "629722000214")
      (description "WR-USB 2.0 Type C, Receptacle, Horizontal, SMT")
      (fields (field (name "MANUFACTURER") "Wurth Elektronik"))
      (libsource (lib "WR-USB") (part "629722000214"))
    )
    (comp (ref "Z1")
      (value "24 MHz")
      (footprint "4-SMD 2.00mm x 1.60mm")
      (description "24 MHz, 10 pF, ±20ppm, 2.00mm x 1.60mm, -40°C ~ 85°C")
      (fields (field (name "MANUFACTURER") "Abracon LLC") (field (name "PARTNUM") "535-10940-1-ND"))
      (libsource (lib "ea_OSC_CLK_GEN") (part "ABM11-24.000MHZ-D2X-T3"))
    )
    (comp (ref "Z2")
      (value "32.768kHz")
      (footprint "ABS7")
      (description "32.768 kHz ±20ppm Crystal 4pF 70 kOhms 3-SMD, No Lead, 3.20mm x 1.50mm, -40°C ~ 85°C")
      (fields
        (field (name "MANUFACTURER") "Citizen Finedevice Co Ltd")
        (field (name "PARTNUM") "300-8868-1-ND")
      )
      (libsource (lib "ea_OSC_CLK_GEN") (part "CM315E32768DZZT-4PF"))
    )
    (comp (ref "Z4")
      (value "32.768 kHz")
      (footprint "ABS7")
      (description "32.768 kHz, 12.5 pF, 70 kOhm, ±20ppm, 3.2 x 1.5 mm, -40°C ~ 85°C")
      (fields (field (name "MANUFACTURER") "Abracon Corporation") (field (name "PARTNUM") "535-9542-1-ND"))
      (libsource (lib "ea_OSC_CLK_GEN") (part "ABS07-32.768KHZ-T"))
    )
  )
  (nets
    (net (code "1") (name "+3V_CARD") (class "Default")
      (node (ref "U10") (pin "B1") (pinfunction "LOAD_B1") (pintype "passive"))
    )
    (net (code "2") (name "+3V_CPU") (class "Default")
      (node (ref "C10") (pin "1") (pinfunction "1_1") (pintype "passive"))
      (node (ref "C11") (pin "1") (pinfunction "1_1") (pintype "passive"))
      (node (ref "C110") (pin "1") (pinfunction "1_1") (pintype "passive"))
      (node (ref "C12") (pin "1") (pinfunction "1_1") (pintype "passive"))
      (node (ref "C13") (pin "1") (pinfunction "1_1") (pintype "passive"))
      (node (ref "C17") (pin "1") (pinfunction "1_1") (pintype "passive"))
      (node (ref "C18") (pin "1") (pinfunction "1_1") (pintype "passive"))
      (node (ref "C19") (pin "1") (pinfunction "1_1") (pintype "passive"))
      (node (ref "C21") (pin "1") (pinfunction "1_1") (pintype "passive"))
      (node (ref "C22") (pin "1") (pinfunction "1_1") (pintype "passive"))
      (node (ref "C26") (pin "1") (pinfunction "1_1") (pintype "passive"))
      (node (ref "C27") (pin "1") (pinfunction "1_1") (pintype "passive"))
      (node (ref "C28") (pin "1") (pinfunction "1_1") (pintype "passive"))
      (node (ref "C30") (pin "1") (pinfunction "1_1") (pintype "passive"))
      (node (ref "C31") (pin "1") (pinfunction "1_1") (pintype "passive"))
      (node (ref "L3") (pin "1") (pinfunction "1_1") (pintype "passive"))
      (node (ref "LED1") (pin "2") (pinfunction "2_2") (pintype "passive"))
      (node (ref "LED2") (pin "2") (pinfunction "2_2") (pintype "passive"))
      (node (ref "LED3") (pin "2") (pinfunction "2_2") (pintype "passive"))
      (node (ref "R23") (pin "1") (pinfunction "1_1") (pintype "passive"))
      (node (ref "R29") (pin "2") (pinfunction "2_2") (pintype "passive"))
      (node (ref "R32") (pin "2") (pinfunction "2_2") (pintype "passive"))
      (node (ref "R34") (pin "2") (pinfunction "2_2") (pintype "passive"))
      (node (ref "R47") (pin "2") (pinfunction "2_2") (pintype "passive"))
      (node (ref "R7") (pin "2") (pinfunction "2_2") (pintype "passive"))
      (node (ref "R8") (pin "2") (pinfunction "2_2") (pintype "passive"))
      (node (ref "R9") (pin "2") (pinfunction "2_2") (pintype "passive"))
      (node (ref "U10") (pin "C1") (pinfunction "VOUT_C1") (pintype "passive"))
      (node (ref "U17") (pin "A13") (pinfunction "VCC_USB_A13") (pintype "power_in"))
      (node (ref "U17") (pin "A8") (pinfunction "VCC_DCDC_A8") (pintype "power_in"))
      (node (ref "U17") (pin "B4") (pinfunction "VCC_B4") (pintype "power_in"))
      (node (ref "U17") (pin "B5") (pinfunction "VCC_B5") (pintype "power_in"))
      (node (ref "U17") (pin "D1") (pinfunction "VCC_D1") (pintype "power_in"))
      (node (ref "U17") (pin "D10") (pinfunction "VCC_D10") (pintype "power_in"))
      (node (ref "U17") (pin "F13") (pinfunction "VCC_USBHS_F13") (pintype "power_in"))
      (node (ref "U17") (pin "H12") (pinfunction "VCC_H12") (pintype "power_in"))
      (node (ref "U17") (pin "H13") (pinfunction "AVCC_USBHS_H13") (pintype "power_in"))
      (node (ref "U17") (pin "H3") (pinfunction "VCC_H3") (pintype "power_in"))
      (node (ref "U17") (pin "L12") (pinfunction "VCC_L12") (pintype "power_in"))
      (node (ref "U17") (pin "L7") (pinfunction "VCC_L7") (pintype "power_in"))
      (node (ref "U17") (pin "M2") (pinfunction "VCC_M2") (pintype "power_in"))
      (node (ref "U17") (pin "P7") (pinfunction "VCC_P7") (pintype "power_in"))
      (node (ref "U4") (pin "13") (pinfunction "VCC_13") (pintype "passive"))
    )
    (net (code "3") (name "+5V") (class "Default")
      (node (ref "C16") (pin "1") (pinfunction "1_1") (pintype "passive"))
      (node (ref "C23") (pin "1") (pinfunction "1_1") (pintype "passive"))
      (node (ref "R17") (pin "1") (pinfunction "1_1") (pintype "passive"))
      (node (ref "R18") (pin "1") (pinfunction "1_1") (pintype "passive"))
      (node (ref "U20") (pin "A2") (pinfunction "VI_A2") (pintype "passive"))
      (node (ref "U20") (pin "B2") (pinfunction "VI_B2") (pintype "passive"))
      (node (ref "U3") (pin "1") (pinfunction "VAC_1") (pintype "power_in"))
      (node (ref "U3") (pin "24") (pinfunction "VBUS_24") (pintype "power_in"))
      (node (ref "VD3") (pin "1") (pinfunction "C_1") (pintype "passive"))
      (node (ref "VD4") (pin "1") (pinfunction "C_1") (pintype "passive"))
    )
    (net (code "4") (name "+VBAT") (class "Default")
      (node (ref "BT1") (pin "1") (pinfunction "1_1") (pintype "passive"))
      (node (ref "BT1") (pin "2") (pinfunction "2_2") (pintype "passive"))
      (node (ref "C34") (pin "2") (pinfunction "2_2") (pintype "passive"))
      (node (ref "R25") (pin "2") (pinfunction "2_2") (pintype "passive"))
      (node (ref "R4") (pin "2") (pinfunction "2_2") (pintype "passive"))
      (node (ref "U5") (pin "A2") (pinfunction "BATT_A2") (pintype "passive"))
      (node (ref "X1") (pin "1") (pinfunction "1_1") (pintype "passive"))
    )
    (net (code "5") (name "+VBUS") (class "Default")
      (node (ref "C3") (pin "2") (pinfunction "2_2") (pintype "passive"))
      (node (ref "R1") (pin "1") (pinfunction "1_1") (pintype "passive"))
      (node (ref "U1") (pin "1") (pinfunction "1_1") (pintype "passive"))
      (node (ref "VD3") (pin "2") (pinfunction "A_2") (pintype "passive"))
    )
    (net (code "6") (name "+VBUSHS") (class "Default")
      (node (ref "C103") (pin "2") (pinfunction "2_2") (pintype "passive"))
      (node (ref "R3") (pin "1") (pinfunction "1_1") (pintype "passive"))
      (node (ref "U2") (pin "1") (pinfunction "1_1") (pintype "passive"))
      (node (ref "U20") (pin "A1") (pinfunction "VO_A1") (pintype "passive"))
      (node (ref "U20") (pin "B1") (pinfunction "VO_B1") (pintype "passive"))
      (node (ref "VD4") (pin "2") (pinfunction "A_2") (pintype "passive"))
      (node (ref "X3") (pin "A4/B9") (pinfunction "VBUS_A4/B9") (pintype "passive"))
      (node (ref "X3") (pin "A9/B4") (pinfunction "VBUS_A9/B4") (pintype "passive"))
    )
    (net (code "7") (name "+VCBAT") (class "Default")
      (node (ref "C73") (pin "2") (pinfunction "2_2") (pintype "passive"))
      (node (ref "R25") (pin "1") (pinfunction "1_1") (pintype "passive"))
      (node (ref "U3") (pin "10") (pinfunction "BATSNS_10") (pintype "passive"))
      (node (ref "U3") (pin "13") (pinfunction "BAT_13") (pintype "power_in"))
      (node (ref "U3") (pin "14") (pinfunction "BAT_14") (pintype "power_in"))
      (node (ref "U5") (pin "B3") (pinfunction "SYS_B3") (pintype "passive"))
    )
    (net (code "8") (name "+VSYS") (class "Default")
      (node (ref "C56") (pin "1") (pinfunction "1_1") (pintype "passive"))
      (node (ref "C60") (pin "1") (pinfunction "1_1") (pintype "passive"))
      (node (ref "L1") (pin "2") (pinfunction "2_2") (pintype "passive"))
      (node (ref "R16") (pin "2") (pinfunction "2_2") (pintype "passive"))
      (node (ref "R17") (pin "2") (pinfunction "2_2") (pintype "passive"))
      (node (ref "R19") (pin "1") (pinfunction "1_1") (pintype "passive"))
      (node (ref "U10") (pin "C3") (pinfunction "VIN_C3") (pintype "passive"))
      (node (ref "U3") (pin "15") (pinfunction "SYS_15") (pintype "power_in"))
      (node (ref "U3") (pin "16") (pinfunction "SYS_16") (pintype "power_in"))
    )
    (net (code "9") (name "/+U4SW") (class "Default")
      (node (ref "C53") (pin "1") (pinfunction "1_1") (pintype "passive"))
      (node (ref "L1") (pin "1") (pinfunction "1_1") (pintype "passive"))
      (node (ref "U3") (pin "19") (pinfunction "SW_19") (pintype "power_in"))
      (node (ref "U3") (pin "20") (pinfunction "SW_20") (pintype "power_in"))
    )
    (net (code "10") (name "/AVCC") (class "Default")
      (node (ref "C99") (pin "1") (pinfunction "1_1") (pintype "passive"))
      (node (ref "L3") (pin "2") (pinfunction "2_2") (pintype "passive"))
      (node (ref "U17") (pin "P8") (pinfunction "AVCC0_P8") (pintype "power_in"))
      (node (ref "U17") (pin "R8") (pinfunction "VREFH_R8") (pintype "power_in"))
      (node (ref "U17") (pin "R9") (pinfunction "VREFH0_R9") (pintype "bidirectional"))
    )
    (net (code "11") (name "/BOOT_MODE") (class "Default")
      (node (ref "BT3") (pin "1") (pinfunction "1_1") (pintype "passive"))
      (node (ref "BT3") (pin "2") (pinfunction "2_2") (pintype "passive"))
      (node (ref "R7") (pin "1") (pinfunction "1_1") (pintype "passive"))
      (node (ref "U17") (pin "C8") (pinfunction "P201/MD_C8") (pintype "bidirectional"))
    )
    (net (code "12") (name "/CARD_PWR_EN") (class "Default")
      (node (ref "U10") (pin "B2") (pinfunction "CTRL_B2") (pintype "passive"))
    )
    (net (code "13") (name "/CHARGER_INT") (class "Default")
      (node (ref "R34") (pin "1") (pinfunction "1_1") (pintype "passive"))
      (node (ref "U3") (pin "7") (pinfunction "INT_7") (pintype "output"))
    )
    (net (code "14") (name "/CLK32768") (class "Default")
      (node (ref "C62") (pin "1") (pinfunction "1_1") (pintype "passive"))
      (node (ref "U17") (pin "J14") (pinfunction "XCOUT_J14") (pintype "bidirectional"))
      (node (ref "Z4") (pin "2") (pinfunction "2_2") (pintype "passive"))
    )
    (net (code "15") (name "/EXTI") (class "Default")
      (node (ref "R27") (pin "1") (pinfunction "1_1") (pintype "passive"))
      (node (ref "R28") (pin "2") (pinfunction "2_2") (pintype "passive"))
      (node (ref "U4") (pin "10") (pinfunction "EXTI_10") (pintype "input"))
    )
    (net (code "16") (name "/LED_B") (class "Default")
      (node (ref "R15") (pin "1") (pinfunction "1_1") (pintype "passive"))
    )
    (net (code "17") (name "/LED_G") (class "Default")
      (node (ref "R14") (pin "1") (pinfunction "1_1") (pintype "passive"))
    )
    (net (code "18") (name "/LED_R") (class "Default")
      (node (ref "R13") (pin "1") (pinfunction "1_1") (pintype "passive"))
    )
    (net (code "19") (name "/NMI") (class "Default")
      (node (ref "BT2") (pin "1") (pinfunction "1_1") (pintype "passive"))
      (node (ref "BT2") (pin "2") (pinfunction "2_2") (pintype "passive"))
      (node (ref "R8") (pin "1") (pinfunction "1_1") (pintype "passive"))
      (node (ref "U17") (pin "B8") (pinfunction "P200/NMI_B8") (pintype "bidirectional"))
    )
    (net (code "20") (name "/PWR_ON") (class "Default")
      (node (ref "U3") (pin "12") (pinfunction "~{QON}_12") (pintype "input"))
      (node (ref "U4") (pin "4") (pinfunction "~{IRQ2}_4") (pintype "output"))
    )
    (net (code "21") (name "/PWR_SEL") (class "Default")
      (node (ref "U3") (pin "2") (pinfunction "PSEL_2") (pintype "input"))
    )
    (net (code "22") (name "/RESET") (class "Default")
      (node (ref "C5") (pin "1") (pinfunction "1_1") (pintype "passive"))
      (node (ref "R9") (pin "1") (pinfunction "1_1") (pintype "passive"))
      (node (ref "U17") (pin "F8") (pinfunction "RES_F8") (pintype "passive"))
      (node (ref "U4") (pin "1") (pinfunction "~{RST}_1") (pintype "output"))
    )
    (net (code "23") (name "/RTC_BATT") (class "Default")
      (node (ref "BAT1") (pin "2") (pinfunction "2_2") (pintype "passive"))
      (node (ref "R12") (pin "2") (pinfunction "2_2") (pintype "passive"))
      (node (ref "R24") (pin "1") (pinfunction "1_1") (pintype "passive"))
    )
    (net (code "24") (name "/RTC_CS") (class "Default")
      (node (ref "U4") (pin "12") (pinfunction "~{CS}_12") (pintype "input"))
    )
    (net (code "25") (name "/RTC_IRQ") (class "Default")
      (node (ref "R23") (pin "2") (pinfunction "2_2") (pintype "passive"))
      (node (ref "U4") (pin "11") (pinfunction "~{IRQ}_11") (pintype "output"))
    )
    (net (code "26") (name "/SCL2") (class "Default")
      (node (ref "R32") (pin "1") (pinfunction "1_1") (pintype "passive"))
      (node (ref "U3") (pin "5") (pinfunction "SCL_5") (pintype "input"))
      (node (ref "U5") (pin "B1") (pinfunction "SCL_B1") (pintype "passive"))
    )
    (net (code "27") (name "/SDA2") (class "Default")
      (node (ref "R29") (pin "1") (pinfunction "1_1") (pintype "passive"))
      (node (ref "U3") (pin "6") (pinfunction "SDA_6") (pintype "bidirectional"))
      (node (ref "U5") (pin "C1") (pinfunction "SDA_C1") (pintype "passive"))
    )
    (net (code "28") (name "/SPI8_MISO") (class "Default")
      (node (ref "U4") (pin "6") (pinfunction "MISO_6") (pintype "output"))
    )
    (net (code "29") (name "/SPI8_MOSI") (class "Default")
      (node (ref "U4") (pin "9") (pinfunction "MOSI_9") (pintype "input"))
    )
    (net (code "30") (name "/SPI8_SCK") (class "Default")
      (node (ref "U4") (pin "7") (pinfunction "SCL_7") (pintype "input"))
    )
    (net (code "31") (name "/SYSV_V") (class "Default")
      (node (ref "C25") (pin "1") (pinfunction "1_1") (pintype "passive"))
      (node (ref "R19") (pin "2") (pinfunction "2_2") (pintype "passive"))
      (node (ref "R21") (pin "1") (pinfunction "1_1") (pintype "passive"))
    )
    (net (code "32") (name "/U5V_V") (class "Default")
      (node (ref "C24") (pin "1") (pinfunction "1_1") (pintype "passive"))
      (node (ref "R18") (pin "2") (pinfunction "2_2") (pintype "passive"))
      (node (ref "R20") (pin "1") (pinfunction "1_1") (pintype "passive"))
    )
    (net (code "33") (name "/USBHS_N") (class "Default")
      (node (ref "U17") (pin "F15") (pinfunction "USBHS_DM_F15") (pintype "bidirectional"))
      (node (ref "U2") (pin "5") (pinfunction "5_5") (pintype "passive"))
      (node (ref "X3") (pin "A7") (pinfunction "D-1_A7") (pintype "passive"))
      (node (ref "X3") (pin "B7") (pinfunction "D-2_B7") (pintype "passive"))
    )
    (net (code "34") (name "/USBHS_P") (class "Default")
      (node (ref "U17") (pin "F14") (pinfunction "USBHS_DP_F14") (pintype "bidirectional"))
      (node (ref "U2") (pin "6") (pinfunction "6_6") (pintype "passive"))
      (node (ref "X3") (pin "A6") (pinfunction "D+1_A6") (pintype "passive"))
      (node (ref "X3") (pin "B6") (pinfunction "D+2_B6") (pintype "passive"))
    )
    (net (code "35") (name "/USBHS_STATE") (class "Default")
      (node (ref "C8") (pin "2") (pinfunction "2_2") (pintype "passive"))
      (node (ref "R11") (pin "1") (pinfunction "1_1") (pintype "passive"))
      (node (ref "R3") (pin "2") (pinfunction "2_2") (pintype "passive"))
    )
    (net (code "36") (name "/USB_N") (class "Default")
      (node (ref "U1") (pin "5") (pinfunction "5_5") (pintype "passive"))
      (node (ref "U17") (pin "B14") (pinfunction "USB_DM_B14") (pintype "bidirectional"))
    )
    (net (code "37") (name "/USB_P") (class "Default")
      (node (ref "U1") (pin "6") (pinfunction "6_6") (pintype "passive"))
      (node (ref "U17") (pin "A14") (pinfunction "USB_DP_A14") (pintype "bidirectional"))
    )
    (net (code "38") (name "/USB_STATE") (class "Default")
      (node (ref "C4") (pin "2") (pinfunction "2_2") (pintype "passive"))
      (node (ref "R1") (pin "2") (pinfunction "2_2") (pintype "passive"))
      (node (ref "R2") (pin "1") (pinfunction "1_1") (pintype "passive"))
    )
    (net (code "39") (name "/VBUSCTRL") (class "Default")
      (node (ref "U20") (pin "C2") (pinfunction "EN_C2") (pintype "passive"))
    )
    (net (code "40") (name "/VSEL1") (class "Default")
      (node (ref "U10") (pin "A3") (pinfunction "VSEL1_A3") (pintype "passive"))
    )
    (net (code "41") (name "/VSEL2") (class "Default")
      (node (ref "U10") (pin "A2") (pinfunction "VSEL2_A2") (pintype "passive"))
    )
    (net (code "42") (name "/VSEL3") (class "Default")
      (node (ref "U10") (pin "A1") (pinfunction "VSEL3_A1") (pintype "passive"))
    )
    (net (code "43") (name "/WDT_RESET") (class "Default")
      (node (ref "U4") (pin "2") (pinfunction "WDI_2") (pintype "input"))
    )
    (net (code "44") (name "GND") (class "Default")
      (node (ref "BAT1") (pin "1") (pinfunction "1_1") (pintype "passive"))
      (node (ref "BT2") (pin "3") (pinfunction "3_3") (pintype "passive"))
      (node (ref "BT2") (pin "4") (pinfunction "4_4") (pintype "passive"))
      (node (ref "BT3") (pin "3") (pinfunction "3_3") (pintype "passive"))
      (node (ref "BT3") (pin "4") (pinfunction "4_4") (pintype "passive"))
      (node (ref "C1") (pin "1") (pinfunction "1_1") (pintype "passive"))
      (node (ref "C10") (pin "2") (pinfunction "2_2") (pintype "passive"))
      (node (ref "C103") (pin "1") (pinfunction "1_1") (pintype "passive"))
      (node (ref "C11") (pin "2") (pinfunction "2_2") (pintype "passive"))
      (node (ref "C110") (pin "2") (pinfunction "2_2") (pintype "passive"))
      (node (ref "C12") (pin "2") (pinfunction "2_2") (pintype "passive"))
      (node (ref "C13") (pin "2") (pinfunction "2_2") (pintype "passive"))
      (node (ref "C14") (pin "2") (pinfunction "2_2") (pintype "passive"))
      (node (ref "C15") (pin "2") (pinfunction "2_2") (pintype "passive"))
      (node (ref "C16") (pin "2") (pinfunction "2_2") (pintype "passive"))
      (node (ref "C17") (pin "2") (pinfunction "2_2") (pintype "passive"))
      (node (ref "C18") (pin "2") (pinfunction "2_2") (pintype "passive"))
      (node (ref "C19") (pin "2") (pinfunction "2_2") (pintype "passive"))
      (node (ref "C2") (pin "2") (pinfunction "2_2") (pintype "passive"))
      (node (ref "C20") (pin "2") (pinfunction "2_2") (pintype "passive"))
      (node (ref "C21") (pin "2") (pinfunction "2_2") (pintype "passive"))
      (node (ref "C22") (pin "2") (pinfunction "2_2") (pintype "passive"))
      (node (ref "C23") (pin "2") (pinfunction "2_2") (pintype "passive"))
      (node (ref "C24") (pin "2") (pinfunction "2_2") (pintype "passive"))
      (node (ref "C25") (pin "2") (pinfunction "2_2") (pintype "passive"))
      (node (ref "C26") (pin "2") (pinfunction "2_2") (pintype "passive"))
      (node (ref "C27") (pin "2") (pinfunction "2_2") (pintype "passive"))
      (node (ref "C28") (pin "2") (pinfunction "2_2") (pintype "passive"))
      (node (ref "C29") (pin "2") (pinfunction "2_2") (pintype "passive"))
      (node (ref "C3") (pin "1") (pinfunction "1_1") (pintype "passive"))
      (node (ref "C30") (pin "2") (pinfunction "2_2") (pintype "passive"))
      (node (ref "C31") (pin "2") (pinfunction "2_2") (pintype "passive"))
      (node (ref "C32") (pin "2") (pinfunction "2_2") (pintype "passive"))
      (node (ref "C33") (pin "2") (pinfunction "2_2") (pintype "passive"))
      (node (ref "C34") (pin "1") (pinfunction "1_1") (pintype "passive"))
      (node (ref "C4") (pin "1") (pinfunction "1_1") (pintype "passive"))
      (node (ref "C5") (pin "2") (pinfunction "2_2") (pintype "passive"))
      (node (ref "C56") (pin "2") (pinfunction "2_2") (pintype "passive"))
      (node (ref "C6") (pin "2") (pinfunction "2_2") (pintype "passive"))
      (node (ref "C60") (pin "2") (pinfunction "2_2") (pintype "passive"))
      (node (ref "C61") (pin "2") (pinfunction "2_2") (pintype "passive"))
      (node (ref "C62") (pin "2") (pinfunction "2_2") (pintype "passive"))
      (node (ref "C7") (pin "2") (pinfunction "2_2") (pintype "passive"))
      (node (ref "C73") (pin "1") (pinfunction "1_1") (pintype "passive"))
      (node (ref "C8") (pin "1") (pinfunction "1_1") (pintype "passive"))
      (node (ref "C9") (pin "2") (pinfunction "2_2") (pintype "passive"))
      (node (ref "C99") (pin "2") (pinfunction "2_2") (pintype "passive"))
      (node (ref "R10") (pin "2") (pinfunction "2_2") (pintype "passive"))
      (node (ref "R11") (pin "2") (pinfunction "2_2") (pintype "passive"))
      (node (ref "R2") (pin "2") (pinfunction "2_2") (pintype "passive"))
      (node (ref "R20") (pin "2") (pinfunction "2_2") (pintype "passive"))
      (node (ref "R21") (pin "2") (pinfunction "2_2") (pintype "passive"))
      (node (ref "R26") (pin "2") (pinfunction "2_2") (pintype "passive"))
      (node (ref "R28") (pin "1") (pinfunction "1_1") (pintype "passive"))
      (node (ref "R41") (pin "1") (pinfunction "1_1") (pintype "passive"))
      (node (ref "R42") (pin "1") (pinfunction "1_1") (pintype "passive"))
      (node (ref "R6") (pin "1") (pinfunction "1_1") (pintype "passive"))
      (node (ref "U1") (pin "2") (pinfunction "2_2") (pintype "passive"))
      (node (ref "U1") (pin "3") (pinfunction "3_3") (pintype "passive"))
      (node (ref "U1") (pin "4") (pinfunction "4_4") (pintype "passive"))
      (node (ref "U1") (pin "7") (pinfunction "7_7") (pintype "passive"))
      (node (ref "U10") (pin "C2") (pinfunction "GND_C2") (pintype "passive"))
      (node (ref "U17") (pin "A4") (pinfunction "VSS_A4") (pintype "power_in"))
      (node (ref "U17") (pin "A5") (pinfunction "VSS_A5") (pintype "power_in"))
      (node (ref "U17") (pin "B10") (pinfunction "VSS_B10") (pintype "power_in"))
      (node (ref "U17") (pin "B13") (pinfunction "VSS_USB_B13") (pintype "power_in"))
      (node (ref "U17") (pin "C10") (pinfunction "VSS_C10") (pintype "power_in"))
      (node (ref "U17") (pin "D2") (pinfunction "VSS_D2") (pintype "power_in"))
      (node (ref "U17") (pin "E15") (pinfunction "VSS_E15") (pintype "power_in"))
      (node (ref "U17") (pin "F12") (pinfunction "VSS1_USBHS_F12") (pintype "power_in"))
      (node (ref "U17") (pin "G12") (pinfunction "VSS2_USBHS_G12") (pintype "power_in"))
      (node (ref "U17") (pin "G14") (pinfunction "AVSS_USBHS_G14") (pintype "power_in"))
      (node (ref "U17") (pin "G15") (pinfunction "PVSS_USBHS_G15") (pintype "power_in"))
      (node (ref "U17") (pin "H2") (pinfunction "VSS_H2") (pintype "power_in"))
      (node (ref "U17") (pin "J13") (pinfunction "VSS_J13") (pintype "power_in"))
      (node (ref "U17") (pin "L11") (pinfunction "VSS_L11") (pintype "power_in"))
      (node (ref "U17") (pin "L8") (pinfunction "VSS_L8") (pintype "power_in"))
      (node (ref "U17") (pin "M1") (pinfunction "VSS_M1") (pintype "power_in"))
      (node (ref "U17") (pin "N8") (pinfunction "VREFL_N8") (pintype "power_in"))
      (node (ref "U17") (pin "N9") (pinfunction "AVSS0_N9") (pintype "power_in"))
      (node (ref "U17") (pin "P9") (pinfunction "VREFL0_P9") (pintype "bidirectional"))
      (node (ref "U17") (pin "R7") (pinfunction "VSS_R7") (pintype "power_in"))
      (node (ref "U2") (pin "2") (pinfunction "2_2") (pintype "passive"))
      (node (ref "U2") (pin "3") (pinfunction "3_3") (pintype "passive"))
      (node (ref "U2") (pin "4") (pinfunction "4_4") (pintype "passive"))
      (node (ref "U2") (pin "7") (pinfunction "7_7") (pintype "passive"))
      (node (ref "U20") (pin "C1") (pinfunction "GND_C1") (pintype "passive"))
      (node (ref "U3") (pin "17") (pinfunction "PGND_17") (pintype "power_in"))
      (node (ref "U3") (pin "18") (pinfunction "PGND_18") (pintype "power_in"))
      (node (ref "U3") (pin "25") (pinfunction "PGND_25") (pintype "power_in"))
      (node (ref "U3") (pin "9") (pinfunction "~{CE}_9") (pintype "input"))
      (node (ref "U4") (pin "17") (pinfunction "GND_17") (pintype "passive"))
      (node (ref "U5") (pin "C3") (pinfunction "GND_C3") (pintype "passive"))
      (node (ref "VD2") (pin "2") (pinfunction "2_2") (pintype "passive"))
      (node (ref "X1") (pin "2") (pinfunction "2_2") (pintype "passive"))
      (node (ref "X3") (pin "A1/B12") (pinfunction "GND_A1/B12") (pintype "passive"))
      (node (ref "X3") (pin "A12/B1") (pinfunction "GND_A12/B1") (pintype "passive"))
      (node (ref "X3") (pin "Shell") (pinfunction "Shield_Shell") (pintype "passive"))
      (node (ref "Z1") (pin "2") (pinfunction "2_2") (pintype "passive"))
      (node (ref "Z1") (pin "4") (pinfunction "4_4") (pintype "passive"))
    )
    (net (code "45") (name "Net-(BT1-Pad3)") (class "Default")
      (node (ref "BT1") (pin "3") (pinfunction "3_3") (pintype "passive"))
      (node (ref "BT1") (pin "4") (pinfunction "4_4") (pintype "passive"))
      (node (ref "R27") (pin "2") (pinfunction "2_2") (pintype "passive"))
    )
    (net (code "46") (name "Net-(L4-Pad2)") (class "Default")
      (node (ref "L4") (pin "2") (pinfunction "2_2") (pintype "passive"))
      (node (ref "U17") (pin "A9") (pinfunction "VLO_A9") (pintype "power_in"))
      (node (ref "U17") (pin "B9") (pinfunction "VLO_B9") (pintype "power_in"))
      (node (ref "VD2") (pin "1") (pinfunction "1_1") (pintype "passive"))
    )
    (net (code "47") (name "Net-(LED1-Pad1)") (class "Default")
      (node (ref "LED1") (pin "1") (pinfunction "1_1") (pintype "passive"))
      (node (ref "R13") (pin "2") (pinfunction "2_2") (pintype "passive"))
    )
    (net (code "48") (name "Net-(LED2-Pad1)") (class "Default")
      (node (ref "LED2") (pin "1") (pinfunction "1_1") (pintype "passive"))
      (node (ref "R14") (pin "2") (pinfunction "2_2") (pintype "passive"))
    )
    (net (code "49") (name "Net-(LED3-Pad1)") (class "Default")
      (node (ref "LED3") (pin "1") (pinfunction "1_1") (pintype "passive"))
      (node (ref "R15") (pin "2") (pinfunction "2_2") (pintype "passive"))
    )
    (net (code "50") (name "Net-(U3-BTST)") (class "Default")
      (node (ref "C53") (pin "2") (pinfunction "2_2") (pintype "passive"))
      (node (ref "U3") (pin "21") (pinfunction "BTST_21") (pintype "power_in"))
    )
    (net (code "51") (name "Net-(U3-PMID)") (class "Default")
      (node (ref "C1") (pin "2") (pinfunction "2_2") (pintype "passive"))
      (node (ref "U3") (pin "23") (pinfunction "PMID_23") (pintype "output"))
    )
    (net (code "52") (name "Net-(U3-REGN)") (class "Default")
      (node (ref "C2") (pin "1") (pinfunction "1_1") (pintype "passive"))
      (node (ref "R5") (pin "2") (pinfunction "2_2") (pintype "passive"))
      (node (ref "U3") (pin "22") (pinfunction "REGN_22") (pintype "power_in"))
    )
    (net (code "53") (name "Net-(U3-TS)") (class "Default")
      (node (ref "R5") (pin "1") (pinfunction "1_1") (pintype "passive"))
      (node (ref "R6") (pin "2") (pinfunction "2_2") (pintype "passive"))
      (node (ref "U3") (pin "11") (pinfunction "TS_11") (pintype "input"))
    )
    (net (code "54") (name "Net-(U4-AF)") (class "Default")
      (node (ref "C32") (pin "1") (pinfunction "1_1") (pintype "passive"))
      (node (ref "U4") (pin "14") (pinfunction "AF_14") (pintype "output"))
    )
    (net (code "55") (name "Net-(U4-VBAT)") (class "Default")
      (node (ref "R24") (pin "2") (pinfunction "2_2") (pintype "passive"))
      (node (ref "U4") (pin "5") (pinfunction "VBAT_5") (pintype "passive"))
    )
    (net (code "56") (name "Net-(U4-XI)") (class "Default")
      (node (ref "U4") (pin "16") (pinfunction "XI_16") (pintype "passive"))
      (node (ref "Z2") (pin "2") (pinfunction "2_2") (pintype "passive"))
    )
    (net (code "57") (name "Net-(U4-XO)") (class "Default")
      (node (ref "U4") (pin "15") (pinfunction "XO_15") (pintype "passive"))
      (node (ref "Z2") (pin "1") (pinfunction "1_1") (pintype "passive"))
    )
    (net (code "58") (name "Net-(U5-REG)") (class "Default")
      (node (ref "C33") (pin "1") (pinfunction "1_1") (pintype "passive"))
      (node (ref "U5") (pin "C2") (pinfunction "REG_C2") (pintype "passive"))
    )
    (net (code "59") (name "Net-(U5-TH)") (class "Default")
      (node (ref "R26") (pin "1") (pinfunction "1_1") (pintype "passive"))
      (node (ref "U5") (pin "A1") (pinfunction "TH_A1") (pintype "passive"))
    )
    (net (code "60") (name "Net-(U10-EN)") (class "Default")
      (node (ref "R16") (pin "1") (pinfunction "1_1") (pintype "passive"))
      (node (ref "U10") (pin "B3") (pinfunction "EN_B3") (pintype "passive"))
    )
    (net (code "61") (name "Net-(U17B-P212{slash}EXTAL)") (class "Default")
      (node (ref "C6") (pin "1") (pinfunction "1_1") (pintype "passive"))
      (node (ref "U17") (pin "H15") (pinfunction "P212/EXTAL_H15") (pintype "bidirectional"))
      (node (ref "Z1") (pin "1") (pinfunction "1_1") (pintype "passive"))
    )
    (net (code "62") (name "Net-(U17B-P213{slash}XTAL)") (class "Default")
      (node (ref "C7") (pin "1") (pinfunction "1_1") (pintype "passive"))
      (node (ref "U17") (pin "H14") (pinfunction "P213/XTAL_H14") (pintype "bidirectional"))
      (node (ref "Z1") (pin "3") (pinfunction "3_3") (pintype "passive"))
    )
    (net (code "63") (name "Net-(U17B-USBHS_RREF)") (class "Default")
      (node (ref "R10") (pin "1") (pinfunction "1_1") (pintype "passive"))
      (node (ref "U17") (pin "G13") (pinfunction "USBHS_RREF_G13") (pintype "power_in"))
    )
    (net (code "64") (name "Net-(U17B-VBATT)") (class "Default")
      (node (ref "R12") (pin "1") (pinfunction "1_1") (pintype "passive"))
      (node (ref "U17") (pin "K14") (pinfunction "VBATT_K14") (pintype "power_in"))
      (node (ref "VD1") (pin "1") (pinfunction "C_1") (pintype "passive"))
    )
    (net (code "65") (name "Net-(U17B-VCL0)") (class "Default")
      (node (ref "C14") (pin "1") (pinfunction "1_1") (pintype "passive"))
      (node (ref "C15") (pin "1") (pinfunction "1_1") (pintype "passive"))
      (node (ref "C20") (pin "1") (pinfunction "1_1") (pintype "passive"))
      (node (ref "C9") (pin "1") (pinfunction "1_1") (pintype "passive"))
      (node (ref "L4") (pin "1") (pinfunction "1_1") (pintype "passive"))
      (node (ref "U17") (pin "A10") (pinfunction "VCL1_A10") (pintype "power_in"))
      (node (ref "U17") (pin "K15") (pinfunction "VCL0_K15") (pintype "bidirectional"))
      (node (ref "U17") (pin "R6") (pinfunction "VCL2_R6") (pintype "power_in"))
    )
    (net (code "66") (name "Net-(U17B-VCL_F)") (class "Default")
      (node (ref "C29") (pin "1") (pinfunction "1_1") (pintype "passive"))
      (node (ref "U17") (pin "H1") (pinfunction "VCL_F_H1") (pintype "power_in"))
    )
    (net (code "67") (name "Net-(U17B-XCIN)") (class "Default")
      (node (ref "C61") (pin "1") (pinfunction "1_1") (pintype "passive"))
      (node (ref "U17") (pin "J15") (pinfunction "XCIN_J15") (pintype "bidirectional"))
      (node (ref "Z4") (pin "1") (pinfunction "1_1") (pintype "passive"))
    )
    (net (code "68") (name "Net-(VD1-A)") (class "Default")
      (node (ref "R4") (pin "1") (pinfunction "1_1") (pintype "passive"))
      (node (ref "R47") (pin "1") (pinfunction "1_1") (pintype "passive"))
      (node (ref "VD1") (pin "2") (pinfunction "A_2") (pintype "passive"))
    )
    (net (code "69") (name "Net-(X3-CC1)") (class "Default")
      (node (ref "R42") (pin "2") (pinfunction "2_2") (pintype "passive"))
      (node (ref "X3") (pin "A5") (pinfunction "CC1_A5") (pintype "passive"))
    )
    (net (code "70") (name "Net-(X3-CC2)") (class "Default")
      (node (ref "R41") (pin "2") (pinfunction "2_2") (pintype "passive"))
      (node (ref "X3") (pin "B5") (pinfunction "CC2_B5") (pintype "passive"))
    )
    (net (code "71") (name "unconnected-(U3-NC-Pad8)") (class "Default")
      (node (ref "U3") (pin "8") (pinfunction "NC_8") (pintype "passive"))
    )
    (net (code "72") (name "unconnected-(U3-STAT-Pad4)") (class "Default")
      (node (ref "U3") (pin "4") (pinfunction "STAT_4") (pintype "output"))
    )
    (net (code "73") (name "unconnected-(U3-~{PG}-Pad3)") (class "Default")
      (node (ref "U3") (pin "3") (pinfunction "~{PG}_3") (pintype "output"))
    )
    (net (code "74") (name "unconnected-(U4-~{EXTR}-Pad3)") (class "Default")
      (node (ref "U4") (pin "3") (pinfunction "~{EXTR}_3") (pintype "input"))
    )
    (net (code "75") (name "unconnected-(U4-~{IRQ3}-Pad8)") (class "Default")
      (node (ref "U4") (pin "8") (pinfunction "~{IRQ3}_8") (pintype "output"))
    )
    (net (code "76") (name "unconnected-(U5-ALRT-PadB2)") (class "Default")
      (node (ref "U5") (pin "B2") (pinfunction "ALRT_B2") (pintype "passive"))
    )
    (net (code "77") (name "unconnected-(U5-NC-PadA3)") (class "Default")
      (node (ref "U5") (pin "A3") (pinfunction "NC_A3") (pintype "passive"))
    )
    (net (code "78") (name "unconnected-(X3-SBU1-PadA8)") (class "Default")
      (node (ref "X3") (pin "A8") (pinfunction "SBU1_A8") (pintype "passive"))
    )
    (net (code "79") (name "unconnected-(X3-SBU2-PadB8)") (class "Default")
      (node (ref "X3") (pin "B8") (pinfunction "SBU2_B8") (pintype "passive"))
    )
  )
)
